# ADC-Q_CHANNEL_GAIN_CONTROL.net
KiCad netlist of a schematic drawn in Altium Designer
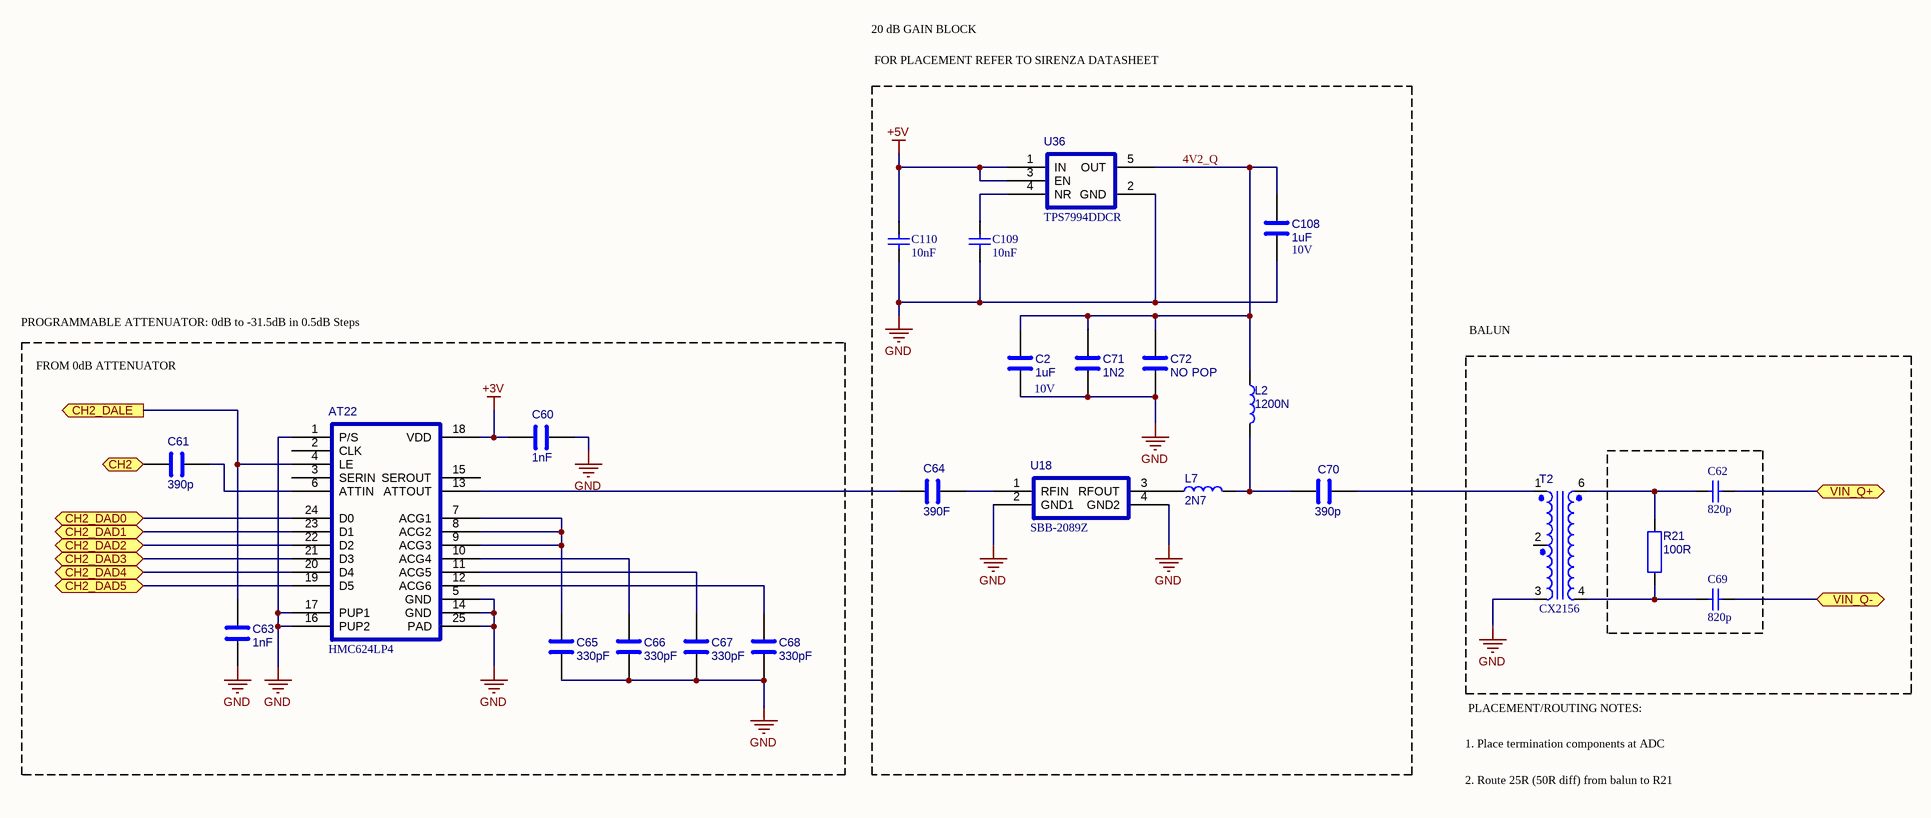
[diagram p0: ADC-Q CHANNEL GAIN CONTROL.SchDoc]

(export (version "E")
  (design (tool "Eeschema 10.0.6"))
  (components
    (comp (ref "AT22")
      (value "HMC624LP4")
      (footprint "QFN50P400X400X100-25USR")
      (description "Broadband 6-bit IC Digital Attenuator")
      (fields
        (field (name "MANUFACTURER") "Hittite")
        (field (name "CREATED_BY") "IN")
        (field (name "CHECKED_BY") "NN")
        (field (name "CHECKED_DATE") "NN-08-2009")
      )
      (libsource (lib "Ishvah-TEMP") (part "HMC624LP4"))
    )
    (comp (ref "C2")
      (value "1uF")
      (footprint "CAPC1632X80USR")
      (description "CAP SMD 0603")
      (fields (field (name "VOLTAGE") "10V") (field (name "CREATED_BY") "*") (field (name "CHECKED_BY") "*"))
      (libsource (lib "Abdus-TEMP") (part "CAP-0603"))
    )
    (comp (ref "C60")
      (value "1nF")
      (footprint "0603")
      (description "CAP SMD 0603")
      (fields
        (field (name "Comment") "Footprint ???")
        (field (name "CREATED_BY") "*")
        (field (name "CHECKED_BY") "*")
      )
      (libsource (lib "Abdus-TEMP") (part "CAP-0603"))
    )
    (comp (ref "C61")
      (value "390p")
      (footprint "CAPC1005X55N")
      (description "CAP SMD 0603")
      (fields (field (name "CREATED_BY") "*") (field (name "CHECKED_BY") "*"))
      (libsource (lib "Abdus-TEMP") (part "CAP-0603"))
    )
    (comp (ref "C62")
      (value "820p")
      (footprint "CAPC1005X55N")
      (description "Capacitor 0402 SMD")
      (fields (field (name "CREATED_BY") "EDA-ASA") (field (name "CHECKED_BY") "*"))
      (libsource (lib "EDA-Passive") (part "cap0402"))
    )
    (comp (ref "C63")
      (value "1nF")
      (footprint "0603")
      (description "CAP SMD 0603")
      (fields (field (name "CREATED_BY") "*") (field (name "CHECKED_BY") "*"))
      (libsource (lib "Abdus-TEMP") (part "CAP-0603"))
    )
    (comp (ref "C64")
      (value "390F")
      (footprint "CAPC1005X55N")
      (description "CAP SMD 0603")
      (fields (field (name "CREATED_BY") "*") (field (name "CHECKED_BY") "*"))
      (libsource (lib "Abdus-TEMP") (part "CAP-0603"))
    )
    (comp (ref "C65")
      (value "330pF")
      (footprint "0603")
      (description "CAP SMD 0603")
      (fields (field (name "CREATED_BY") "*") (field (name "CHECKED_BY") "*"))
      (libsource (lib "Abdus-TEMP") (part "CAP-0603"))
    )
    (comp (ref "C66")
      (value "330pF")
      (footprint "0603")
      (description "CAP SMD 0603")
      (fields (field (name "CREATED_BY") "*") (field (name "CHECKED_BY") "*"))
      (libsource (lib "Abdus-TEMP") (part "CAP-0603"))
    )
    (comp (ref "C67")
      (value "330pF")
      (footprint "0603")
      (description "CAP SMD 0603")
      (fields (field (name "CREATED_BY") "*") (field (name "CHECKED_BY") "*"))
      (libsource (lib "Abdus-TEMP") (part "CAP-0603"))
    )
    (comp (ref "C68")
      (value "330pF")
      (footprint "0603")
      (description "CAP SMD 0603")
      (fields (field (name "CREATED_BY") "*") (field (name "CHECKED_BY") "*"))
      (libsource (lib "Abdus-TEMP") (part "CAP-0603"))
    )
    (comp (ref "C69")
      (value "820p")
      (footprint "CAPC1005X55N")
      (description "Capacitor 0402 SMD")
      (fields (field (name "CREATED_BY") "EDA-ASA") (field (name "CHECKED_BY") "*"))
      (libsource (lib "EDA-Passive") (part "cap0402"))
    )
    (comp (ref "C70")
      (value "390p")
      (footprint "CAPC1005X55N")
      (description "CAP SMD 0603")
      (fields
        (field (name "Comment") "Footprint ???")
        (field (name "CREATED_BY") "*")
        (field (name "CHECKED_BY") "*")
      )
      (libsource (lib "Abdus-TEMP") (part "CAP-0603"))
    )
    (comp (ref "C71")
      (value "1N2")
      (footprint "CAPC1005X55N")
      (description "CAP SMD 0603")
      (fields (field (name "CREATED_BY") "*") (field (name "CHECKED_BY") "*"))
      (libsource (lib "Abdus-TEMP") (part "CAP-0603"))
    )
    (comp (ref "C72")
      (value "NO POP")
      (footprint "CAPC1005X55N")
      (description "CAP SMD 0603")
      (fields (field (name "CREATED_BY") "*") (field (name "CHECKED_BY") "*"))
      (libsource (lib "Abdus-TEMP") (part "CAP-0603"))
    )
    (comp (ref "C108")
      (value "1uF")
      (footprint "CAPC1632X80USR")
      (description "CAP SMD 0603")
      (fields
        (field (name "VOLTAGE") "10V")
        (field (name "Comment") "Footprint ???")
        (field (name "CREATED_BY") "*")
        (field (name "CHECKED_BY") "*")
      )
      (libsource (lib "Abdus-TEMP") (part "CAP-0603"))
    )
    (comp (ref "C109")
      (value "10nF")
      (footprint "CAPC1005X55N")
      (description "Capacitor 0402 SMD")
      (fields (field (name "CREATED_BY") "EDA-ASA") (field (name "CHECKED_BY") "*"))
      (libsource (lib "EDA-Passive") (part "cap0402"))
    )
    (comp (ref "C110")
      (value "10nF")
      (footprint "CAPC1005X55N")
      (description "Capacitor 0402 SMD")
      (fields (field (name "CREATED_BY") "EDA-ASA") (field (name "CHECKED_BY") "*"))
      (libsource (lib "EDA-Passive") (part "cap0402"))
    )
    (comp (ref "L2")
      (value "1200N")
      (footprint "INDM2520X160N")
      (description "CHOKE")
      (fields (field (name "CREATED_BY") "EDA-ASA") (field (name "CHECKED_BY") "*"))
      (libsource (lib "EDA_GenericSymbols") (part "CHOKE"))
    )
    (comp (ref "L7")
      (value "2N7")
      (footprint "INDC1005X60N")
      (description "CHOKE")
      (fields (field (name "CREATED_BY") "EDA-ASA") (field (name "CHECKED_BY") "*"))
      (libsource (lib "EDA_GenericSymbols") (part "CHOKE"))
    )
    (comp (ref "R21")
      (value "100R")
      (footprint "RESC1005X40N")
      (description "RESISTOR SMD 0805")
      (fields (field (name "CREATED_BY") "*") (field (name "CHECKED_BY") "NN"))
      (libsource (lib "EDA_Passive") (part "RES-0805"))
    )
    (comp (ref "T2")
      (value "CX2156")
      (footprint "PULSE_KAYAK")
      (description "TRANSFORMER WIDEBAND RF APPLICATION")
      (fields
        (field (name "VOLTAGE") "???")
        (field (name "MANUFACTURER_PN") "CX2156")
        (field (name "CREATED_BY") "*")
        (field (name "CHECKED_BY") "*")
      )
      (libsource (lib "Charles-TEMP") (part "CX2156"))
    )
    (comp (ref "U18")
      (value "SBB-2089Z")
      (footprint "SIRENZA_SOT89")
      (description "High performance InaGaP HBT MMIC amplfier")
      (fields
        (field (name "MANUFACTURER") "Sirenza Micodevices")
        (field (name "CREATED_BY") "IN")
        (field (name "CHECKED_BY") "*")
      )
      (libsource (lib "Ishvah-TEMP") (part "SBB-2089Z"))
    )
    (comp (ref "U36")
      (value "TPS7994DDCR")
      (footprint "SOT95P280X110-5USR")
      (description "Low Quiescent Current, Ultra-Low Noise Dropout Linear Regulator")
      (fields
        (field (name "MANUFACTURER") "TI")
        (field (name "CREATED_BY") "IN")
        (field (name "CHECKED_BY") "*")
      )
      (libsource (lib "Ishvah-TEMP") (part "TPS7994DDCR"))
    )
  )
  (nets
    (net (code "1") (name "+3V") (class "Default")
      (node (ref "AT22") (pin "18") (pinfunction "VDD_18") (pintype "passive"))
      (node (ref "C60") (pin "1") (pinfunction "1_1") (pintype "passive"))
    )
    (net (code "2") (name "+5V") (class "Default")
      (node (ref "C110") (pin "1") (pinfunction "1_1") (pintype "passive"))
      (node (ref "U36") (pin "1") (pinfunction "IN_1") (pintype "passive"))
      (node (ref "U36") (pin "3") (pinfunction "EN_3") (pintype "passive"))
    )
    (net (code "3") (name "/4V2_Q") (class "Default")
      (node (ref "C108") (pin "1") (pinfunction "1_1") (pintype "passive"))
      (node (ref "C2") (pin "1") (pinfunction "1_1") (pintype "passive"))
      (node (ref "C71") (pin "1") (pinfunction "1_1") (pintype "passive"))
      (node (ref "C72") (pin "1") (pinfunction "1_1") (pintype "passive"))
      (node (ref "L2") (pin "1") (pinfunction "1_1") (pintype "passive"))
      (node (ref "U36") (pin "5") (pinfunction "OUT_5") (pintype "passive"))
    )
    (net (code "4") (name "/CH2") (class "Default")
      (node (ref "C61") (pin "1") (pinfunction "1_1") (pintype "passive"))
    )
    (net (code "5") (name "/CH2_DAD0") (class "Default")
      (node (ref "AT22") (pin "24") (pinfunction "D0_24") (pintype "passive"))
    )
    (net (code "6") (name "/CH2_DAD1") (class "Default")
      (node (ref "AT22") (pin "23") (pinfunction "D1_23") (pintype "passive"))
    )
    (net (code "7") (name "/CH2_DAD2") (class "Default")
      (node (ref "AT22") (pin "22") (pinfunction "D2_22") (pintype "passive"))
    )
    (net (code "8") (name "/CH2_DAD3") (class "Default")
      (node (ref "AT22") (pin "21") (pinfunction "D3_21") (pintype "passive"))
    )
    (net (code "9") (name "/CH2_DAD4") (class "Default")
      (node (ref "AT22") (pin "20") (pinfunction "D4_20") (pintype "passive"))
    )
    (net (code "10") (name "/CH2_DAD5") (class "Default")
      (node (ref "AT22") (pin "19") (pinfunction "D5_19") (pintype "passive"))
    )
    (net (code "11") (name "/CH2_DALE") (class "Default")
      (node (ref "AT22") (pin "4") (pinfunction "LE_4") (pintype "passive"))
      (node (ref "C63") (pin "1") (pinfunction "1_1") (pintype "passive"))
    )
    (net (code "12") (name "/VIN_Q+") (class "Default")
      (node (ref "C62") (pin "2") (pinfunction "2_2") (pintype "passive"))
    )
    (net (code "13") (name "/VIN_Q-") (class "Default")
      (node (ref "C69") (pin "2") (pinfunction "2_2") (pintype "passive"))
    )
    (net (code "14") (name "GND") (class "Default")
      (node (ref "AT22") (pin "1") (pinfunction "P/S_1") (pintype "passive"))
      (node (ref "AT22") (pin "14") (pinfunction "GND_14") (pintype "passive"))
      (node (ref "AT22") (pin "16") (pinfunction "PUP2_16") (pintype "passive"))
      (node (ref "AT22") (pin "17") (pinfunction "PUP1_17") (pintype "passive"))
      (node (ref "AT22") (pin "25") (pinfunction "PAD_25") (pintype "passive"))
      (node (ref "AT22") (pin "5") (pinfunction "GND_5") (pintype "passive"))
      (node (ref "C108") (pin "2") (pinfunction "2_2") (pintype "passive"))
      (node (ref "C109") (pin "2") (pinfunction "2_2") (pintype "passive"))
      (node (ref "C110") (pin "2") (pinfunction "2_2") (pintype "passive"))
      (node (ref "C2") (pin "2") (pinfunction "2_2") (pintype "passive"))
      (node (ref "C60") (pin "2") (pinfunction "2_2") (pintype "passive"))
      (node (ref "C63") (pin "2") (pinfunction "2_2") (pintype "passive"))
      (node (ref "C65") (pin "2") (pinfunction "2_2") (pintype "passive"))
      (node (ref "C66") (pin "2") (pinfunction "2_2") (pintype "passive"))
      (node (ref "C67") (pin "2") (pinfunction "2_2") (pintype "passive"))
      (node (ref "C68") (pin "2") (pinfunction "2_2") (pintype "passive"))
      (node (ref "C71") (pin "2") (pinfunction "2_2") (pintype "passive"))
      (node (ref "C72") (pin "2") (pinfunction "2_2") (pintype "passive"))
      (node (ref "T2") (pin "3") (pinfunction "3_3") (pintype "passive"))
      (node (ref "U18") (pin "2") (pinfunction "GND1_2") (pintype "passive"))
      (node (ref "U18") (pin "4") (pinfunction "GND2_4") (pintype "passive"))
      (node (ref "U36") (pin "2") (pinfunction "GND_2") (pintype "passive"))
    )
    (net (code "15") (name "Net-(AT22-ACG1)") (class "Default")
      (node (ref "AT22") (pin "7") (pinfunction "ACG1_7") (pintype "passive"))
      (node (ref "AT22") (pin "8") (pinfunction "ACG2_8") (pintype "passive"))
      (node (ref "AT22") (pin "9") (pinfunction "ACG3_9") (pintype "passive"))
      (node (ref "C65") (pin "1") (pinfunction "1_1") (pintype "passive"))
    )
    (net (code "16") (name "Net-(AT22-ACG4)") (class "Default")
      (node (ref "AT22") (pin "10") (pinfunction "ACG4_10") (pintype "passive"))
      (node (ref "C66") (pin "1") (pinfunction "1_1") (pintype "passive"))
    )
    (net (code "17") (name "Net-(AT22-ACG5)") (class "Default")
      (node (ref "AT22") (pin "11") (pinfunction "ACG5_11") (pintype "passive"))
      (node (ref "C67") (pin "1") (pinfunction "1_1") (pintype "passive"))
    )
    (net (code "18") (name "Net-(AT22-ACG6)") (class "Default")
      (node (ref "AT22") (pin "12") (pinfunction "ACG6_12") (pintype "passive"))
      (node (ref "C68") (pin "1") (pinfunction "1_1") (pintype "passive"))
    )
    (net (code "19") (name "Net-(AT22-ATTIN)") (class "Default")
      (node (ref "AT22") (pin "6") (pinfunction "ATTIN_6") (pintype "passive"))
      (node (ref "C61") (pin "2") (pinfunction "2_2") (pintype "passive"))
    )
    (net (code "20") (name "Net-(AT22-ATTOUT)") (class "Default")
      (node (ref "AT22") (pin "13") (pinfunction "ATTOUT_13") (pintype "passive"))
      (node (ref "C64") (pin "1") (pinfunction "1_1") (pintype "passive"))
    )
    (net (code "21") (name "Net-(C62-Pad1)") (class "Default")
      (node (ref "C62") (pin "1") (pinfunction "1_1") (pintype "passive"))
      (node (ref "R21") (pin "1") (pinfunction "1_1") (pintype "passive"))
      (node (ref "T2") (pin "6") (pinfunction "6_6") (pintype "passive"))
    )
    (net (code "22") (name "Net-(C69-Pad1)") (class "Default")
      (node (ref "C69") (pin "1") (pinfunction "1_1") (pintype "passive"))
      (node (ref "R21") (pin "2") (pinfunction "2_2") (pintype "passive"))
      (node (ref "T2") (pin "4") (pinfunction "4_4") (pintype "passive"))
    )
    (net (code "23") (name "Net-(C70-Pad1)") (class "Default")
      (node (ref "C70") (pin "1") (pinfunction "1_1") (pintype "passive"))
      (node (ref "L2") (pin "2") (pinfunction "2_2") (pintype "passive"))
      (node (ref "L7") (pin "2") (pinfunction "2_2") (pintype "passive"))
    )
    (net (code "24") (name "Net-(C70-Pad2)") (class "Default")
      (node (ref "C70") (pin "2") (pinfunction "2_2") (pintype "passive"))
      (node (ref "T2") (pin "1") (pinfunction "1_1") (pintype "passive"))
    )
    (net (code "25") (name "Net-(U18-RFIN)") (class "Default")
      (node (ref "C64") (pin "2") (pinfunction "2_2") (pintype "passive"))
      (node (ref "U18") (pin "1") (pinfunction "RFIN_1") (pintype "passive"))
    )
    (net (code "26") (name "Net-(U18-RFOUT)") (class "Default")
      (node (ref "L7") (pin "1") (pinfunction "1_1") (pintype "passive"))
      (node (ref "U18") (pin "3") (pinfunction "RFOUT_3") (pintype "passive"))
    )
    (net (code "27") (name "Net-(U36-NR)") (class "Default")
      (node (ref "C109") (pin "1") (pinfunction "1_1") (pintype "passive"))
      (node (ref "U36") (pin "4") (pinfunction "NR_4") (pintype "passive"))
    )
    (net (code "28") (name "unconnected-(AT22-CLK-Pad2)") (class "Default")
      (node (ref "AT22") (pin "2") (pinfunction "CLK_2") (pintype "passive"))
    )
    (net (code "29") (name "unconnected-(AT22-SERIN-Pad3)") (class "Default")
      (node (ref "AT22") (pin "3") (pinfunction "SERIN_3") (pintype "passive"))
    )
    (net (code "30") (name "unconnected-(AT22-SEROUT-Pad15)") (class "Default")
      (node (ref "AT22") (pin "15") (pinfunction "SEROUT_15") (pintype "passive"))
    )
    (net (code "31") (name "unconnected-(T2-Pad2)") (class "Default")
      (node (ref "T2") (pin "2") (pinfunction "2_2") (pintype "passive"))
    )
  )
)
